# EL_MBRD_T01.net
KiCad netlist of a schematic drawn in Altium Designer
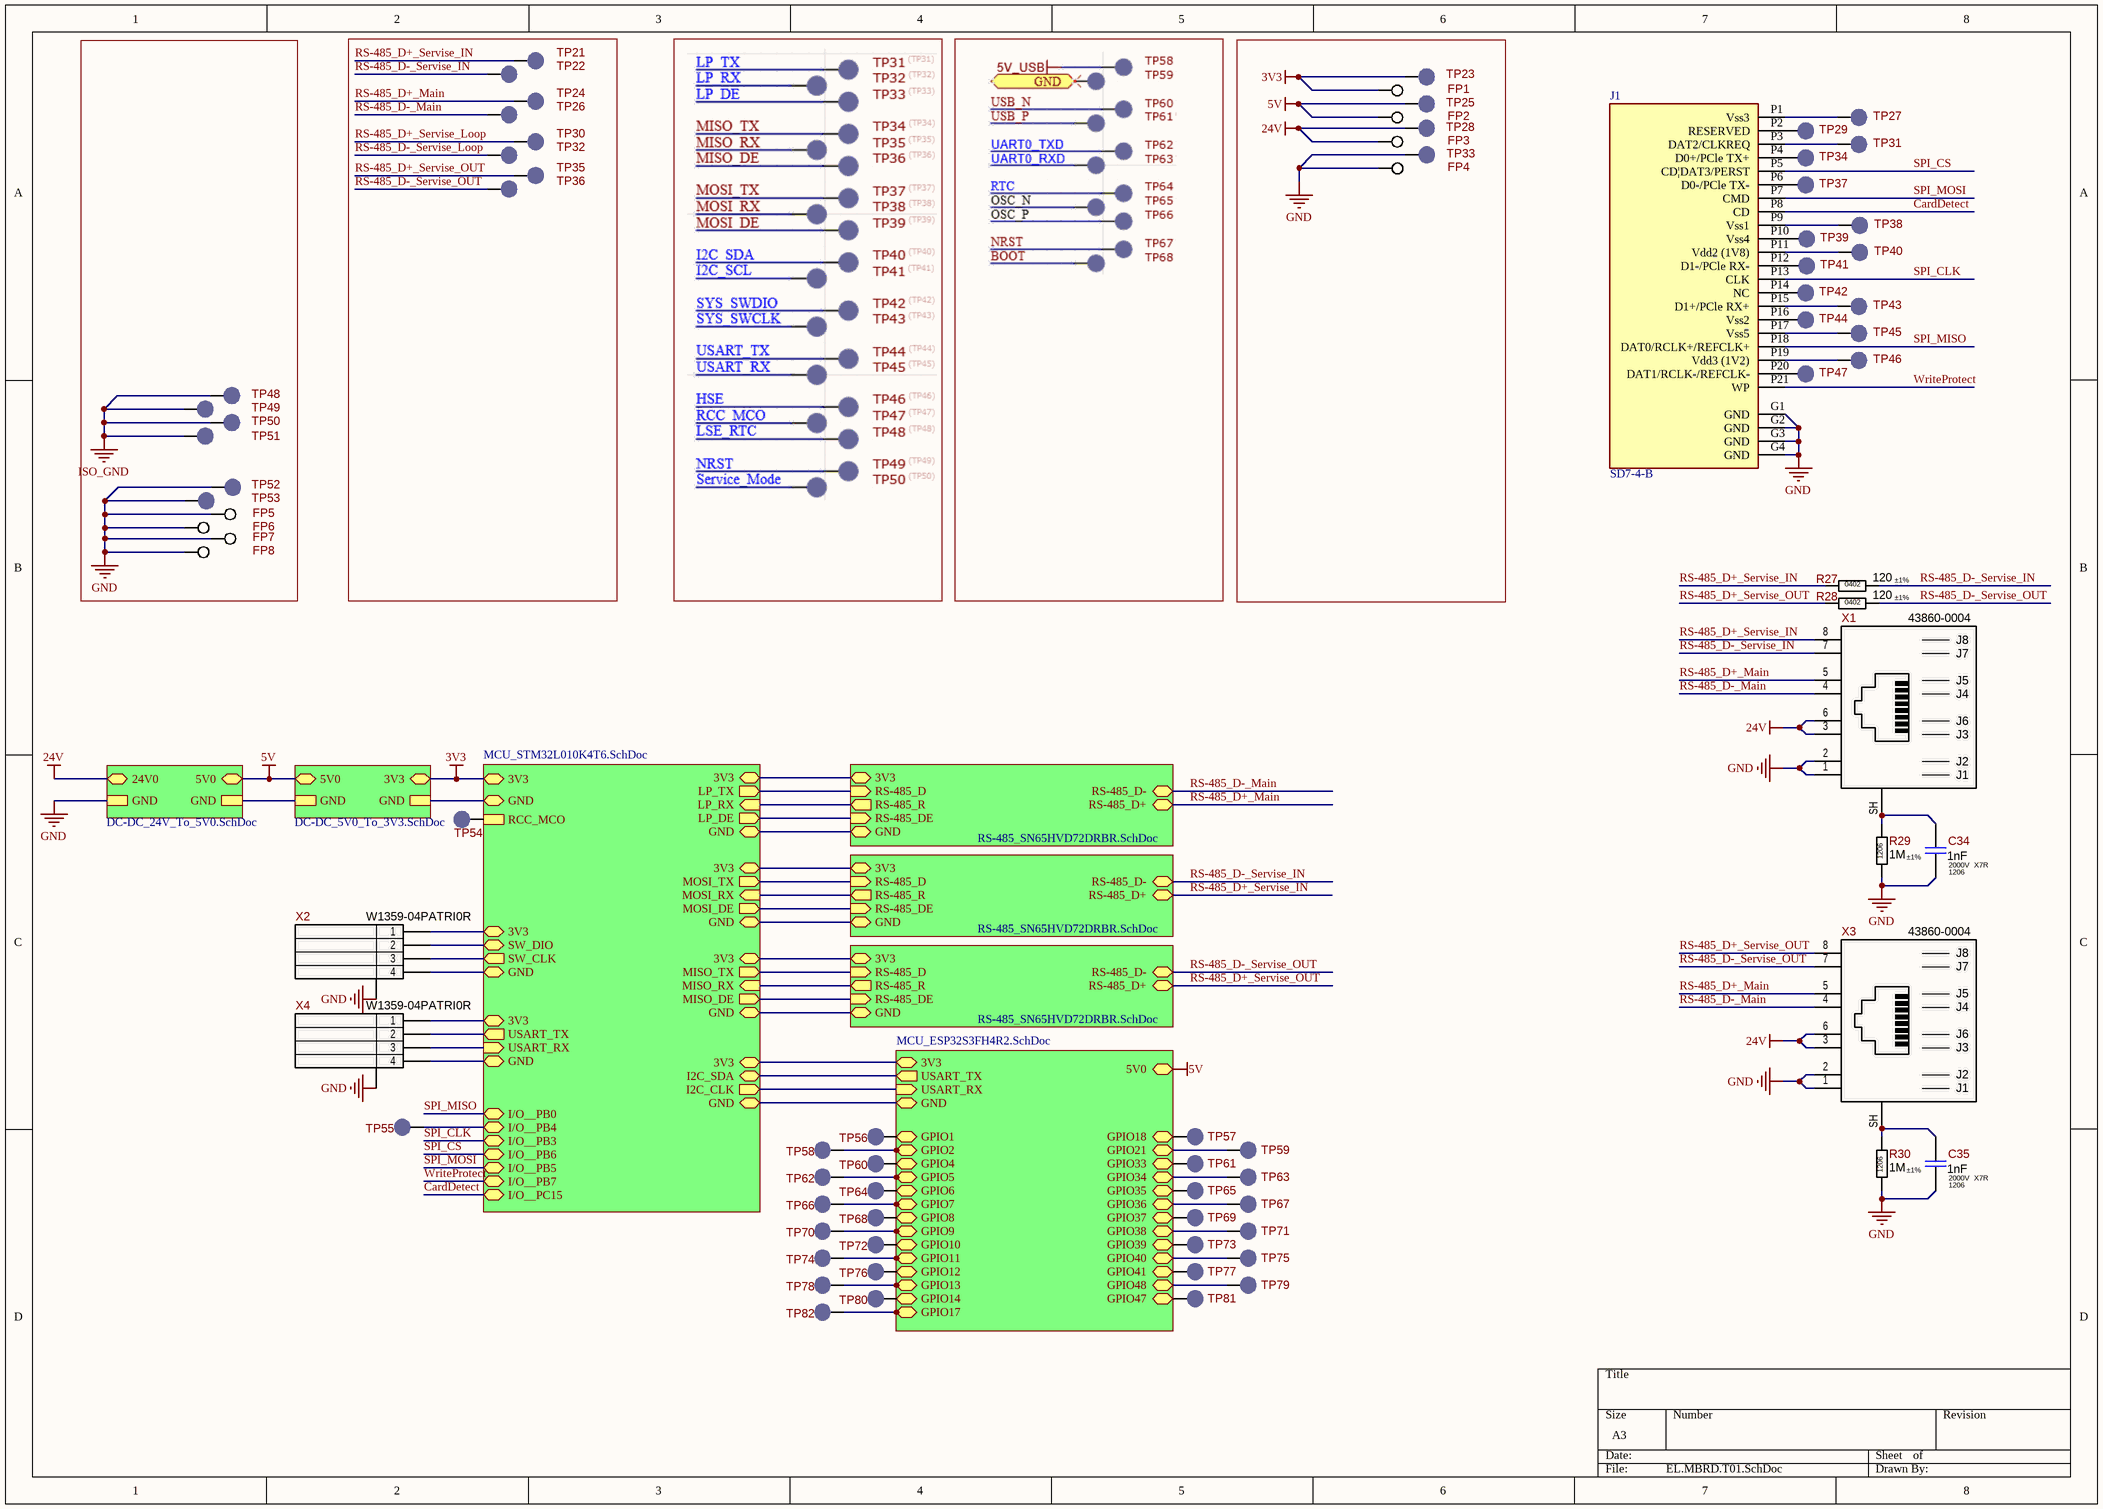
[diagram p0: EL.MBRD.T01.SchDoc]

(export (version "E")
  (design (tool "Eeschema 10.0.6"))
  (components
    (comp (ref "C34")
      (value "1nF")
      (footprint "CAP-1206(3216)X125T20")
      (description "1nF 2000V X7R ±10% 1206 Ceramic Capacitor RoHS")
      (fields
        (field (name "PACKAGE") "1206")
        (field (name "VOLTAGE") "2000V")
        (field (name "DIELECTRIC TYPE") "X7R")
        (field (name "PART NUMBER") "CC1206KKX7RDBB102")
        (field (name "MANUFACTURER") "Yageo")
      )
      (libsource (lib "EL.XXX.T01") (part "Capacitor-NonPolar"))
    )
    (comp (ref "C35")
      (value "1nF")
      (footprint "CAP-1206(3216)X125T20")
      (description "1nF 2000V X7R ±10% 1206 Ceramic Capacitor RoHS")
      (fields
        (field (name "PACKAGE") "1206")
        (field (name "VOLTAGE") "2000V")
        (field (name "DIELECTRIC TYPE") "X7R")
        (field (name "PART NUMBER") "CC1206KKX7RDBB102")
        (field (name "MANUFACTURER") "Yageo")
      )
      (libsource (lib "EL.XXX.T01") (part "Capacitor-NonPolar"))
    )
    (comp (ref "FP1")
      (value "PAD-1.1mm")
      (footprint "PAD-1.1mm")
      (description "1.1mm Pad for Plug-In or Receptacle")
      (fields (field (name "MANUFACTURER") "NONE"))
      (libsource (lib "EL.XXX.T01") (part "Pad"))
    )
    (comp (ref "FP2")
      (value "PAD-1.1mm")
      (footprint "PAD-1.1mm")
      (description "1.1mm Pad for Plug-In or Receptacle")
      (fields (field (name "MANUFACTURER") "NONE"))
      (libsource (lib "EL.XXX.T01") (part "Pad"))
    )
    (comp (ref "FP3")
      (value "PAD-1.1mm")
      (footprint "PAD-1.1mm")
      (description "1.1mm Pad for Plug-In or Receptacle")
      (fields (field (name "MANUFACTURER") "NONE"))
      (libsource (lib "EL.XXX.T01") (part "Pad"))
    )
    (comp (ref "FP4")
      (value "PAD-1.1mm")
      (footprint "PAD-1.1mm")
      (description "1.1mm Pad for Plug-In or Receptacle")
      (fields (field (name "MANUFACTURER") "NONE"))
      (libsource (lib "EL.XXX.T01") (part "Pad"))
    )
    (comp (ref "FP5")
      (value "PAD-1.1mm")
      (footprint "PAD-1.1mm")
      (description "1.1mm Pad for Plug-In or Receptacle")
      (fields (field (name "MANUFACTURER") "NONE"))
      (libsource (lib "EL.XXX.T01") (part "Pad"))
    )
    (comp (ref "FP6")
      (value "PAD-1.1mm")
      (footprint "PAD-1.1mm")
      (description "1.1mm Pad for Plug-In or Receptacle")
      (fields (field (name "MANUFACTURER") "NONE"))
      (libsource (lib "EL.XXX.T01") (part "Pad"))
    )
    (comp (ref "FP7")
      (value "PAD-1.1mm")
      (footprint "PAD-1.1mm")
      (description "1.1mm Pad for Plug-In or Receptacle")
      (fields (field (name "MANUFACTURER") "NONE"))
      (libsource (lib "EL.XXX.T01") (part "Pad"))
    )
    (comp (ref "FP8")
      (value "PAD-1.1mm")
      (footprint "PAD-1.1mm")
      (description "1.1mm Pad for Plug-In or Receptacle")
      (fields (field (name "MANUFACTURER") "NONE"))
      (libsource (lib "EL.XXX.T01") (part "Pad"))
    )
    (comp (ref "J1")
      (value "SD7-4-B")
      (footprint "SAMESKY_SD7-4-B")
      (description "21 (18 + 3) Position Card Connector Secure Digital - SD Surface Mount, Right Angle Gold")
      (fields (field (name "MF") "Same Sky (Formerly CUI Devices)"))
      (libsource (lib "EL.XXX.T01") (part "SD7-4-B"))
    )
    (comp (ref "R27")
      (value "120")
      (footprint "R_ANY_CHIP_0402_HI")
      (description "120 Ohms ±1% 1/16W 0402 Thick Film Resistor")
      (fields
        (field (name "TOLERANCE") "±1%")
        (field (name "PACKAGE") "0402")
        (field (name "PART NUMBER") "RC0402FR-07120RL")
        (field (name "MANUFACTURER") "Yageo")
      )
      (libsource (lib "EL.XXX.T01") (part "Resistor"))
    )
    (comp (ref "R28")
      (value "120")
      (footprint "R_ANY_CHIP_0402_HI")
      (description "120 Ohms ±1% 1/16W 0402 Thick Film Resistor")
      (fields
        (field (name "TOLERANCE") "±1%")
        (field (name "PACKAGE") "0402")
        (field (name "PART NUMBER") "RC0402FR-07120RL")
        (field (name "MANUFACTURER") "Yageo")
      )
      (libsource (lib "EL.XXX.T01") (part "Resistor"))
    )
    (comp (ref "R29")
      (value "1M")
      (footprint "CHV1206-Series")
      (description "1 MOhms ±1%, 1/4W 1206 Thick Film Resistor")
      (fields
        (field (name "TOLERANCE") "±1%")
        (field (name "PACKAGE") "1206")
        (field (name "PART NUMBER") "CHV1206-FX-1004ELF")
        (field (name "MANUFACTURER") "Bourns")
      )
      (libsource (lib "EL.XXX.T01") (part "Resistor"))
    )
    (comp (ref "R30")
      (value "1M")
      (footprint "CHV1206-Series")
      (description "1 MOhms ±1%, 1/4W 1206 Thick Film Resistor")
      (fields
        (field (name "TOLERANCE") "±1%")
        (field (name "PACKAGE") "1206")
        (field (name "PART NUMBER") "CHV1206-FX-1004ELF")
        (field (name "MANUFACTURER") "Bourns")
      )
      (libsource (lib "EL.XXX.T01") (part "Resistor"))
    )
    (comp (ref "TP21")
      (value "LED_LINK")
      (footprint "TP_SMD_2mm")
      (description "Test Point SMD Pad 1.0mm/1.5mm/2mm")
      (fields (field (name "PART NUMBER") "TP-PAD-SMD"))
      (libsource (lib "EL.XXX.T01") (part "Test-Point-SMD-1"))
    )
    (comp (ref "TP22")
      (value "LED_LINK")
      (footprint "TP_SMD_2mm")
      (description "Test Point SMD Pad 1.0mm/1.5mm/2mm")
      (fields (field (name "PART NUMBER") "TP-PAD-SMD"))
      (libsource (lib "EL.XXX.T01") (part "Test-Point-SMD-1"))
    )
    (comp (ref "TP23")
      (value "LED_LINK")
      (footprint "TP_SMD_2mm")
      (description "Test Point SMD Pad 1.0mm/1.5mm/2mm")
      (fields (field (name "PART NUMBER") "TP-PAD-SMD"))
      (libsource (lib "EL.XXX.T01") (part "Test-Point-SMD-1"))
    )
    (comp (ref "TP24")
      (value "LED_LINK")
      (footprint "TP_SMD_2mm")
      (description "Test Point SMD Pad 1.0mm/1.5mm/2mm")
      (fields (field (name "PART NUMBER") "TP-PAD-SMD"))
      (libsource (lib "EL.XXX.T01") (part "Test-Point-SMD-1"))
    )
    (comp (ref "TP25")
      (value "LED_LINK")
      (footprint "TP_SMD_2mm")
      (description "Test Point SMD Pad 1.0mm/1.5mm/2mm")
      (fields (field (name "PART NUMBER") "TP-PAD-SMD"))
      (libsource (lib "EL.XXX.T01") (part "Test-Point-SMD-1"))
    )
    (comp (ref "TP26")
      (value "LED_LINK")
      (footprint "TP_SMD_2mm")
      (description "Test Point SMD Pad 1.0mm/1.5mm/2mm")
      (fields (field (name "PART NUMBER") "TP-PAD-SMD"))
      (libsource (lib "EL.XXX.T01") (part "Test-Point-SMD-1"))
    )
    (comp (ref "TP27")
      (value "LED_LINK")
      (footprint "TP_SMD_2mm")
      (description "Test Point SMD Pad 1.0mm/1.5mm/2mm")
      (fields (field (name "PART NUMBER") "TP-PAD-SMD"))
      (libsource (lib "EL.XXX.T01") (part "Test-Point-SMD-1"))
    )
    (comp (ref "TP28")
      (value "LED_LINK")
      (footprint "TP_SMD_2mm")
      (description "Test Point SMD Pad 1.0mm/1.5mm/2mm")
      (fields (field (name "PART NUMBER") "TP-PAD-SMD"))
      (libsource (lib "EL.XXX.T01") (part "Test-Point-SMD-1"))
    )
    (comp (ref "TP29")
      (value "LED_LINK")
      (footprint "TP_SMD_2mm")
      (description "Test Point SMD Pad 1.0mm/1.5mm/2mm")
      (fields (field (name "PART NUMBER") "TP-PAD-SMD"))
      (libsource (lib "EL.XXX.T01") (part "Test-Point-SMD-1"))
    )
    (comp (ref "TP30")
      (value "LED_LINK")
      (footprint "TP_SMD_2mm")
      (description "Test Point SMD Pad 1.0mm/1.5mm/2mm")
      (fields (field (name "PART NUMBER") "TP-PAD-SMD"))
      (libsource (lib "EL.XXX.T01") (part "Test-Point-SMD-1"))
    )
    (comp (ref "TP31")
      (value "LED_LINK")
      (footprint "TP_SMD_2mm")
      (description "Test Point SMD Pad 1.0mm/1.5mm/2mm")
      (fields (field (name "PART NUMBER") "TP-PAD-SMD"))
      (libsource (lib "EL.XXX.T01") (part "Test-Point-SMD-1"))
    )
    (comp (ref "TP32")
      (value "LED_LINK")
      (footprint "TP_SMD_2mm")
      (description "Test Point SMD Pad 1.0mm/1.5mm/2mm")
      (fields (field (name "PART NUMBER") "TP-PAD-SMD"))
      (libsource (lib "EL.XXX.T01") (part "Test-Point-SMD-1"))
    )
    (comp (ref "TP33")
      (value "LED_LINK")
      (footprint "TP_SMD_2mm")
      (description "Test Point SMD Pad 1.0mm/1.5mm/2mm")
      (fields (field (name "PART NUMBER") "TP-PAD-SMD"))
      (libsource (lib "EL.XXX.T01") (part "Test-Point-SMD-1"))
    )
    (comp (ref "TP34")
      (value "LED_LINK")
      (footprint "TP_SMD_2mm")
      (description "Test Point SMD Pad 1.0mm/1.5mm/2mm")
      (fields (field (name "PART NUMBER") "TP-PAD-SMD"))
      (libsource (lib "EL.XXX.T01") (part "Test-Point-SMD-1"))
    )
    (comp (ref "TP35")
      (value "LED_LINK")
      (footprint "TP_SMD_2mm")
      (description "Test Point SMD Pad 1.0mm/1.5mm/2mm")
      (fields (field (name "PART NUMBER") "TP-PAD-SMD"))
      (libsource (lib "EL.XXX.T01") (part "Test-Point-SMD-1"))
    )
    (comp (ref "TP36")
      (value "LED_LINK")
      (footprint "TP_SMD_2mm")
      (description "Test Point SMD Pad 1.0mm/1.5mm/2mm")
      (fields (field (name "PART NUMBER") "TP-PAD-SMD"))
      (libsource (lib "EL.XXX.T01") (part "Test-Point-SMD-1"))
    )
    (comp (ref "TP37")
      (value "LED_LINK")
      (footprint "TP_SMD_2mm")
      (description "Test Point SMD Pad 1.0mm/1.5mm/2mm")
      (fields (field (name "PART NUMBER") "TP-PAD-SMD"))
      (libsource (lib "EL.XXX.T01") (part "Test-Point-SMD-1"))
    )
    (comp (ref "TP38")
      (value "LED_LINK")
      (footprint "TP_SMD_2mm")
      (description "Test Point SMD Pad 1.0mm/1.5mm/2mm")
      (fields (field (name "PART NUMBER") "TP-PAD-SMD"))
      (libsource (lib "EL.XXX.T01") (part "Test-Point-SMD-1"))
    )
    (comp (ref "TP39")
      (value "LED_LINK")
      (footprint "TP_SMD_2mm")
      (description "Test Point SMD Pad 1.0mm/1.5mm/2mm")
      (fields (field (name "PART NUMBER") "TP-PAD-SMD"))
      (libsource (lib "EL.XXX.T01") (part "Test-Point-SMD-1"))
    )
    (comp (ref "TP40")
      (value "LED_LINK")
      (footprint "TP_SMD_2mm")
      (description "Test Point SMD Pad 1.0mm/1.5mm/2mm")
      (fields (field (name "PART NUMBER") "TP-PAD-SMD"))
      (libsource (lib "EL.XXX.T01") (part "Test-Point-SMD-1"))
    )
    (comp (ref "TP41")
      (value "LED_LINK")
      (footprint "TP_SMD_2mm")
      (description "Test Point SMD Pad 1.0mm/1.5mm/2mm")
      (fields (field (name "PART NUMBER") "TP-PAD-SMD"))
      (libsource (lib "EL.XXX.T01") (part "Test-Point-SMD-1"))
    )
    (comp (ref "TP42")
      (value "LED_LINK")
      (footprint "TP_SMD_2mm")
      (description "Test Point SMD Pad 1.0mm/1.5mm/2mm")
      (fields (field (name "PART NUMBER") "TP-PAD-SMD"))
      (libsource (lib "EL.XXX.T01") (part "Test-Point-SMD-1"))
    )
    (comp (ref "TP43")
      (value "LED_LINK")
      (footprint "TP_SMD_2mm")
      (description "Test Point SMD Pad 1.0mm/1.5mm/2mm")
      (fields (field (name "PART NUMBER") "TP-PAD-SMD"))
      (libsource (lib "EL.XXX.T01") (part "Test-Point-SMD-1"))
    )
    (comp (ref "TP44")
      (value "LED_LINK")
      (footprint "TP_SMD_2mm")
      (description "Test Point SMD Pad 1.0mm/1.5mm/2mm")
      (fields (field (name "PART NUMBER") "TP-PAD-SMD"))
      (libsource (lib "EL.XXX.T01") (part "Test-Point-SMD-1"))
    )
    (comp (ref "TP45")
      (value "LED_LINK")
      (footprint "TP_SMD_2mm")
      (description "Test Point SMD Pad 1.0mm/1.5mm/2mm")
      (fields (field (name "PART NUMBER") "TP-PAD-SMD"))
      (libsource (lib "EL.XXX.T01") (part "Test-Point-SMD-1"))
    )
    (comp (ref "TP46")
      (value "LED_LINK")
      (footprint "TP_SMD_2mm")
      (description "Test Point SMD Pad 1.0mm/1.5mm/2mm")
      (fields (field (name "PART NUMBER") "TP-PAD-SMD"))
      (libsource (lib "EL.XXX.T01") (part "Test-Point-SMD-1"))
    )
    (comp (ref "TP47")
      (value "LED_LINK")
      (footprint "TP_SMD_2mm")
      (description "Test Point SMD Pad 1.0mm/1.5mm/2mm")
      (fields (field (name "PART NUMBER") "TP-PAD-SMD"))
      (libsource (lib "EL.XXX.T01") (part "Test-Point-SMD-1"))
    )
    (comp (ref "TP48")
      (value "LED_LINK")
      (footprint "TP_SMD_2mm")
      (description "Test Point SMD Pad 1.0mm/1.5mm/2mm")
      (fields (field (name "PART NUMBER") "TP-PAD-SMD"))
      (libsource (lib "EL.XXX.T01") (part "Test-Point-SMD-1"))
    )
    (comp (ref "TP49")
      (value "LED_LINK")
      (footprint "TP_SMD_2mm")
      (description "Test Point SMD Pad 1.0mm/1.5mm/2mm")
      (fields (field (name "PART NUMBER") "TP-PAD-SMD"))
      (libsource (lib "EL.XXX.T01") (part "Test-Point-SMD-1"))
    )
    (comp (ref "TP50")
      (value "LED_LINK")
      (footprint "TP_SMD_2mm")
      (description "Test Point SMD Pad 1.0mm/1.5mm/2mm")
      (fields (field (name "PART NUMBER") "TP-PAD-SMD"))
      (libsource (lib "EL.XXX.T01") (part "Test-Point-SMD-1"))
    )
    (comp (ref "TP51")
      (value "LED_LINK")
      (footprint "TP_SMD_2mm")
      (description "Test Point SMD Pad 1.0mm/1.5mm/2mm")
      (fields (field (name "PART NUMBER") "TP-PAD-SMD"))
      (libsource (lib "EL.XXX.T01") (part "Test-Point-SMD-1"))
    )
    (comp (ref "TP52")
      (value "LED_LINK")
      (footprint "TP_SMD_2mm")
      (description "Test Point SMD Pad 1.0mm/1.5mm/2mm")
      (fields (field (name "PART NUMBER") "TP-PAD-SMD"))
      (libsource (lib "EL.XXX.T01") (part "Test-Point-SMD-1"))
    )
    (comp (ref "TP53")
      (value "LED_LINK")
      (footprint "TP_SMD_2mm")
      (description "Test Point SMD Pad 1.0mm/1.5mm/2mm")
      (fields (field (name "PART NUMBER") "TP-PAD-SMD"))
      (libsource (lib "EL.XXX.T01") (part "Test-Point-SMD-1"))
    )
    (comp (ref "TP54")
      (value "LED_LINK")
      (footprint "TP_SMD_2mm")
      (description "Test Point SMD Pad 1.0mm/1.5mm/2mm")
      (fields (field (name "PART NUMBER") "TP-PAD-SMD"))
      (libsource (lib "EL.XXX.T01") (part "Test-Point-SMD-1"))
    )
    (comp (ref "TP55")
      (value "LED_LINK")
      (footprint "TP_SMD_2mm")
      (description "Test Point SMD Pad 1.0mm/1.5mm/2mm")
      (fields (field (name "PART NUMBER") "TP-PAD-SMD"))
      (libsource (lib "EL.XXX.T01") (part "Test-Point-SMD-1"))
    )
    (comp (ref "TP56")
      (value "LED_LINK")
      (footprint "TP_SMD_2mm")
      (description "Test Point SMD Pad 1.0mm/1.5mm/2mm")
      (fields (field (name "PART NUMBER") "TP-PAD-SMD"))
      (libsource (lib "EL.XXX.T01") (part "Test-Point-SMD-1"))
    )
    (comp (ref "TP57")
      (value "LED_LINK")
      (footprint "TP_SMD_2mm")
      (description "Test Point SMD Pad 1.0mm/1.5mm/2mm")
      (fields (field (name "PART NUMBER") "TP-PAD-SMD"))
      (libsource (lib "EL.XXX.T01") (part "Test-Point-SMD-1"))
    )
    (comp (ref "TP58")
      (value "LED_LINK")
      (footprint "TP_SMD_2mm")
      (description "Test Point SMD Pad 1.0mm/1.5mm/2mm")
      (fields (field (name "PART NUMBER") "TP-PAD-SMD"))
      (libsource (lib "EL.XXX.T01") (part "Test-Point-SMD-1"))
    )
    (comp (ref "TP59")
      (value "LED_LINK")
      (footprint "TP_SMD_2mm")
      (description "Test Point SMD Pad 1.0mm/1.5mm/2mm")
      (fields (field (name "PART NUMBER") "TP-PAD-SMD"))
      (libsource (lib "EL.XXX.T01") (part "Test-Point-SMD-1"))
    )
    (comp (ref "TP60")
      (value "LED_LINK")
      (footprint "TP_SMD_2mm")
      (description "Test Point SMD Pad 1.0mm/1.5mm/2mm")
      (fields (field (name "PART NUMBER") "TP-PAD-SMD"))
      (libsource (lib "EL.XXX.T01") (part "Test-Point-SMD-1"))
    )
    (comp (ref "TP61")
      (value "LED_LINK")
      (footprint "TP_SMD_2mm")
      (description "Test Point SMD Pad 1.0mm/1.5mm/2mm")
      (fields (field (name "PART NUMBER") "TP-PAD-SMD"))
      (libsource (lib "EL.XXX.T01") (part "Test-Point-SMD-1"))
    )
    (comp (ref "TP62")
      (value "LED_LINK")
      (footprint "TP_SMD_2mm")
      (description "Test Point SMD Pad 1.0mm/1.5mm/2mm")
      (fields (field (name "PART NUMBER") "TP-PAD-SMD"))
      (libsource (lib "EL.XXX.T01") (part "Test-Point-SMD-1"))
    )
    (comp (ref "TP63")
      (value "LED_LINK")
      (footprint "TP_SMD_2mm")
      (description "Test Point SMD Pad 1.0mm/1.5mm/2mm")
      (fields (field (name "PART NUMBER") "TP-PAD-SMD"))
      (libsource (lib "EL.XXX.T01") (part "Test-Point-SMD-1"))
    )
    (comp (ref "TP64")
      (value "LED_LINK")
      (footprint "TP_SMD_2mm")
      (description "Test Point SMD Pad 1.0mm/1.5mm/2mm")
      (fields (field (name "PART NUMBER") "TP-PAD-SMD"))
      (libsource (lib "EL.XXX.T01") (part "Test-Point-SMD-1"))
    )
    (comp (ref "TP65")
      (value "LED_LINK")
      (footprint "TP_SMD_2mm")
      (description "Test Point SMD Pad 1.0mm/1.5mm/2mm")
      (fields (field (name "PART NUMBER") "TP-PAD-SMD"))
      (libsource (lib "EL.XXX.T01") (part "Test-Point-SMD-1"))
    )
    (comp (ref "TP66")
      (value "LED_LINK")
      (footprint "TP_SMD_2mm")
      (description "Test Point SMD Pad 1.0mm/1.5mm/2mm")
      (fields (field (name "PART NUMBER") "TP-PAD-SMD"))
      (libsource (lib "EL.XXX.T01") (part "Test-Point-SMD-1"))
    )
    (comp (ref "TP67")
      (value "LED_LINK")
      (footprint "TP_SMD_2mm")
      (description "Test Point SMD Pad 1.0mm/1.5mm/2mm")
      (fields (field (name "PART NUMBER") "TP-PAD-SMD"))
      (libsource (lib "EL.XXX.T01") (part "Test-Point-SMD-1"))
    )
    (comp (ref "TP68")
      (value "LED_LINK")
      (footprint "TP_SMD_2mm")
      (description "Test Point SMD Pad 1.0mm/1.5mm/2mm")
      (fields (field (name "PART NUMBER") "TP-PAD-SMD"))
      (libsource (lib "EL.XXX.T01") (part "Test-Point-SMD-1"))
    )
    (comp (ref "TP69")
      (value "LED_LINK")
      (footprint "TP_SMD_2mm")
      (description "Test Point SMD Pad 1.0mm/1.5mm/2mm")
      (fields (field (name "PART NUMBER") "TP-PAD-SMD"))
      (libsource (lib "EL.XXX.T01") (part "Test-Point-SMD-1"))
    )
    (comp (ref "TP70")
      (value "LED_LINK")
      (footprint "TP_SMD_2mm")
      (description "Test Point SMD Pad 1.0mm/1.5mm/2mm")
      (fields (field (name "PART NUMBER") "TP-PAD-SMD"))
      (libsource (lib "EL.XXX.T01") (part "Test-Point-SMD-1"))
    )
    (comp (ref "TP71")
      (value "LED_LINK")
      (footprint "TP_SMD_2mm")
      (description "Test Point SMD Pad 1.0mm/1.5mm/2mm")
      (fields (field (name "PART NUMBER") "TP-PAD-SMD"))
      (libsource (lib "EL.XXX.T01") (part "Test-Point-SMD-1"))
    )
    (comp (ref "TP72")
      (value "LED_LINK")
      (footprint "TP_SMD_2mm")
      (description "Test Point SMD Pad 1.0mm/1.5mm/2mm")
      (fields (field (name "PART NUMBER") "TP-PAD-SMD"))
      (libsource (lib "EL.XXX.T01") (part "Test-Point-SMD-1"))
    )
    (comp (ref "TP73")
      (value "LED_LINK")
      (footprint "TP_SMD_2mm")
      (description "Test Point SMD Pad 1.0mm/1.5mm/2mm")
      (fields (field (name "PART NUMBER") "TP-PAD-SMD"))
      (libsource (lib "EL.XXX.T01") (part "Test-Point-SMD-1"))
    )
    (comp (ref "TP74")
      (value "LED_LINK")
      (footprint "TP_SMD_2mm")
      (description "Test Point SMD Pad 1.0mm/1.5mm/2mm")
      (fields (field (name "PART NUMBER") "TP-PAD-SMD"))
      (libsource (lib "EL.XXX.T01") (part "Test-Point-SMD-1"))
    )
    (comp (ref "TP75")
      (value "LED_LINK")
      (footprint "TP_SMD_2mm")
      (description "Test Point SMD Pad 1.0mm/1.5mm/2mm")
      (fields (field (name "PART NUMBER") "TP-PAD-SMD"))
      (libsource (lib "EL.XXX.T01") (part "Test-Point-SMD-1"))
    )
    (comp (ref "TP76")
      (value "LED_LINK")
      (footprint "TP_SMD_2mm")
      (description "Test Point SMD Pad 1.0mm/1.5mm/2mm")
      (fields (field (name "PART NUMBER") "TP-PAD-SMD"))
      (libsource (lib "EL.XXX.T01") (part "Test-Point-SMD-1"))
    )
    (comp (ref "TP77")
      (value "LED_LINK")
      (footprint "TP_SMD_2mm")
      (description "Test Point SMD Pad 1.0mm/1.5mm/2mm")
      (fields (field (name "PART NUMBER") "TP-PAD-SMD"))
      (libsource (lib "EL.XXX.T01") (part "Test-Point-SMD-1"))
    )
    (comp (ref "TP78")
      (value "LED_LINK")
      (footprint "TP_SMD_2mm")
      (description "Test Point SMD Pad 1.0mm/1.5mm/2mm")
      (fields (field (name "PART NUMBER") "TP-PAD-SMD"))
      (libsource (lib "EL.XXX.T01") (part "Test-Point-SMD-1"))
    )
    (comp (ref "TP79")
      (value "LED_LINK")
      (footprint "TP_SMD_2mm")
      (description "Test Point SMD Pad 1.0mm/1.5mm/2mm")
      (fields (field (name "PART NUMBER") "TP-PAD-SMD"))
      (libsource (lib "EL.XXX.T01") (part "Test-Point-SMD-1"))
    )
    (comp (ref "TP80")
      (value "LED_LINK")
      (footprint "TP_SMD_2mm")
      (description "Test Point SMD Pad 1.0mm/1.5mm/2mm")
      (fields (field (name "PART NUMBER") "TP-PAD-SMD"))
      (libsource (lib "EL.XXX.T01") (part "Test-Point-SMD-1"))
    )
    (comp (ref "TP81")
      (value "LED_LINK")
      (footprint "TP_SMD_2mm")
      (description "Test Point SMD Pad 1.0mm/1.5mm/2mm")
      (fields (field (name "PART NUMBER") "TP-PAD-SMD"))
      (libsource (lib "EL.XXX.T01") (part "Test-Point-SMD-1"))
    )
    (comp (ref "TP82")
      (value "LED_LINK")
      (footprint "TP_SMD_2mm")
      (description "Test Point SMD Pad 1.0mm/1.5mm/2mm")
      (fields (field (name "PART NUMBER") "TP-PAD-SMD"))
      (libsource (lib "EL.XXX.T01") (part "Test-Point-SMD-1"))
    )
    (comp (ref "X1")
      (value "43860-0004")
      (footprint "43860-0004")
      (description "RJ45 8P8C Shielded Cat 3 10 Base-T Connector")
      (fields (field (name "PART NUMBER") "43860-0004") (field (name "MANUFACTURER") "Molex"))
      (libsource (lib "EL.XXX.T01") (part "43860-0004"))
    )
    (comp (ref "X2")
      (value "W1359-04PATRI0R")
      (footprint "W1359-04PATXI0R_DBG")
      (description "1.25mm Wire-to-Board Header, Vertical, SMT, 4 pin")
      (fields
        (field (name "PART NUMBER") "W1359-04PATRI0R")
        (field (name "MANUFACTURER") "Hsuan Mao Technology")
      )
      (libsource (lib "EL.XXX.T01") (part "General-4-Pin-MP"))
    )
    (comp (ref "X3")
      (value "43860-0004")
      (footprint "43860-0004")
      (description "RJ45 8P8C Shielded Cat 3 10 Base-T Connector")
      (fields (field (name "PART NUMBER") "43860-0004") (field (name "MANUFACTURER") "Molex"))
      (libsource (lib "EL.XXX.T01") (part "43860-0004"))
    )
    (comp (ref "X4")
      (value "W1359-04PATRI0R")
      (footprint "W1359-04PATXI0R_DBG")
      (description "1.25mm Wire-to-Board Header, Vertical, SMT, 4 pin")
      (fields
        (field (name "PART NUMBER") "W1359-04PATRI0R")
        (field (name "MANUFACTURER") "Hsuan Mao Technology")
      )
      (libsource (lib "EL.XXX.T01") (part "General-4-Pin-MP"))
    )
  )
  (nets
    (net (code "4") (name "/3V3_3") (class "Default")
      (node (ref "X2") (pin "1") (pinfunction "1_1") (pintype "passive"))
    )
    (net (code "6") (name "/3V3_5") (class "Default")
      (node (ref "X4") (pin "1") (pinfunction "1_1") (pintype "passive"))
    )
    (net (code "8") (name "/CardDetect") (class "Default")
      (node (ref "J1") (pin "P8") (pinfunction "CD_P8") (pintype "passive"))
    )
    (net (code "9") (name "/GND") (class "Default")
      (node (ref "X2") (pin "4") (pinfunction "4_4") (pintype "passive"))
    )
    (net (code "14") (name "/GND_5") (class "Default")
      (node (ref "X4") (pin "4") (pinfunction "4_4") (pintype "passive"))
    )
    (net (code "19") (name "/GPIO2") (class "Default") (node (ref "TP58") (pin "1") (pintype "passive")))
    (net (code "21") (name "/GPIO5") (class "Default") (node (ref "TP62") (pin "1") (pintype "passive")))
    (net (code "23") (name "/GPIO7") (class "Default") (node (ref "TP66") (pin "1") (pintype "passive")))
    (net (code "25") (name "/GPIO9") (class "Default") (node (ref "TP70") (pin "1") (pintype "passive")))
    (net (code "27") (name "/GPIO11") (class "Default") (node (ref "TP74") (pin "1") (pintype "passive")))
    (net (code "29") (name "/GPIO13") (class "Default") (node (ref "TP78") (pin "1") (pintype "passive")))
    (net (code "31") (name "/GPIO17") (class "Default") (node (ref "TP82") (pin "1") (pintype "passive")))
    (net (code "46") (name "/I{slash}O__PB4") (class "Default")
      (node (ref "TP55") (pin "1") (pintype "passive"))
    )
    (net (code "53") (name "/RCC_MCO") (class "Default") (node (ref "TP54") (pin "1") (pintype "passive")))
    (net (code "54") (name "/RS-485_D+_Main") (class "Default")
      (node (ref "TP24") (pin "1") (pintype "passive"))
      (node (ref "X1") (pin "5") (pinfunction "CT_5") (pintype "passive"))
      (node (ref "X3") (pin "5") (pinfunction "CT_5") (pintype "passive"))
    )
    (net (code "55") (name "/RS-485_D+_Servise_IN") (class "Default")
      (node (ref "R27") (pin "1") (pintype "passive"))
      (node (ref "TP21") (pin "1") (pintype "passive"))
      (node (ref "X1") (pin "8") (pinfunction "TD2+_8") (pintype "passive"))
    )
    (net (code "56") (name "/RS-485_D+_Servise_Loop") (class "Default")
      (node (ref "TP30") (pin "1") (pintype "passive"))
    )
    (net (code "57") (name "/RS-485_D+_Servise_OUT") (class "Default")
      (node (ref "R28") (pin "1") (pintype "passive"))
      (node (ref "TP35") (pin "1") (pintype "passive"))
      (node (ref "X3") (pin "8") (pinfunction "TD2+_8") (pintype "passive"))
    )
    (net (code "58") (name "/RS-485_D-_Main") (class "Default")
      (node (ref "TP26") (pin "1") (pintype "passive"))
      (node (ref "X1") (pin "4") (pinfunction "TD3+_4") (pintype "passive"))
      (node (ref "X3") (pin "4") (pinfunction "TD3+_4") (pintype "passive"))
    )
    (net (code "59") (name "/RS-485_D-_Servise_IN") (class "Default")
      (node (ref "R27") (pin "2") (pintype "passive"))
      (node (ref "TP22") (pin "1") (pintype "passive"))
      (node (ref "X1") (pin "7") (pinfunction "TD2-_7") (pintype "passive"))
    )
    (net (code "60") (name "/RS-485_D-_Servise_Loop") (class "Default")
      (node (ref "TP32") (pin "1") (pintype "passive"))
    )
    (net (code "61") (name "/RS-485_D-_Servise_OUT") (class "Default")
      (node (ref "R28") (pin "2") (pintype "passive"))
      (node (ref "TP36") (pin "1") (pintype "passive"))
      (node (ref "X3") (pin "7") (pinfunction "TD2-_7") (pintype "passive"))
    )
    (net (code "65") (name "/SPI_CLK") (class "Default")
      (node (ref "J1") (pin "P13") (pinfunction "CLK_P13") (pintype "passive"))
    )
    (net (code "66") (name "/SPI_CS") (class "Default")
      (node (ref "J1") (pin "P5") (pinfunction "CD¦DAT3/PERST_P5") (pintype "passive"))
    )
    (net (code "67") (name "/SPI_MISO") (class "Default")
      (node (ref "J1") (pin "P18") (pinfunction "DAT0/RCLK+/REFCLK+_P18") (pintype "passive"))
    )
    (net (code "69") (name "/SW_CLK") (class "Default")
      (node (ref "X2") (pin "3") (pinfunction "3_3") (pintype "passive"))
    )
    (net (code "70") (name "/SW_DIO") (class "Default")
      (node (ref "X2") (pin "2") (pinfunction "2_2") (pintype "passive"))
    )
    (net (code "71") (name "/USART_RX") (class "Default")
      (node (ref "X4") (pin "3") (pinfunction "3_3") (pintype "passive"))
    )
    (net (code "72") (name "/USART_TX") (class "Default")
      (node (ref "X4") (pin "2") (pinfunction "2_2") (pintype "passive"))
    )
    (net (code "74") (name "/WriteProtect") (class "Default")
      (node (ref "J1") (pin "P21") (pinfunction "WP_P21") (pintype "passive"))
    )
    (net (code "75") (name "3V3") (class "Default")
      (node (ref "FP1") (pin "1") (pintype "passive"))
      (node (ref "TP23") (pin "1") (pintype "passive"))
    )
    (net (code "76") (name "5V") (class "Default")
      (node (ref "FP2") (pin "1") (pintype "passive"))
      (node (ref "TP25") (pin "1") (pintype "passive"))
    )
    (net (code "77") (name "24V") (class "Default")
      (node (ref "FP3") (pin "1") (pintype "passive"))
      (node (ref "TP28") (pin "1") (pintype "passive"))
      (node (ref "X1") (pin "3") (pinfunction "TD3-_3") (pintype "passive"))
      (node (ref "X1") (pin "6") (pinfunction "CT_6") (pintype "passive"))
      (node (ref "X3") (pin "3") (pinfunction "TD3-_3") (pintype "passive"))
      (node (ref "X3") (pin "6") (pinfunction "CT_6") (pintype "passive"))
    )
    (net (code "78") (name "GND") (class "Default")
      (node (ref "C34") (pin "2") (pinfunction "2_2") (pintype "passive"))
      (node (ref "C35") (pin "2") (pinfunction "2_2") (pintype "passive"))
      (node (ref "FP4") (pin "1") (pintype "passive"))
      (node (ref "FP5") (pin "1") (pintype "passive"))
      (node (ref "FP6") (pin "1") (pintype "passive"))
      (node (ref "FP7") (pin "1") (pintype "passive"))
      (node (ref "FP8") (pin "1") (pintype "passive"))
      (node (ref "J1") (pin "G1") (pinfunction "GND_G1") (pintype "power_in"))
      (node (ref "J1") (pin "G2") (pinfunction "GND_G2") (pintype "power_in"))
      (node (ref "J1") (pin "G3") (pinfunction "GND_G3") (pintype "power_in"))
      (node (ref "J1") (pin "G4") (pinfunction "GND_G4") (pintype "power_in"))
      (node (ref "R29") (pin "2") (pintype "passive"))
      (node (ref "R30") (pin "2") (pintype "passive"))
      (node (ref "TP33") (pin "1") (pintype "passive"))
      (node (ref "TP52") (pin "1") (pintype "passive"))
      (node (ref "TP53") (pin "1") (pintype "passive"))
      (node (ref "X1") (pin "1") (pinfunction "TD4-_1") (pintype "passive"))
      (node (ref "X1") (pin "2") (pinfunction "TD4+_2") (pintype "passive"))
      (node (ref "X2") (pin "MP") (pinfunction "MountPad_MP") (pintype "passive"))
      (node (ref "X3") (pin "1") (pinfunction "TD4-_1") (pintype "passive"))
      (node (ref "X3") (pin "2") (pinfunction "TD4+_2") (pintype "passive"))
      (node (ref "X4") (pin "MP") (pinfunction "MountPad_MP") (pintype "passive"))
    )
    (net (code "79") (name "ISO_GND") (class "Default")
      (node (ref "TP48") (pin "1") (pintype "passive"))
      (node (ref "TP49") (pin "1") (pintype "passive"))
      (node (ref "TP50") (pin "1") (pintype "passive"))
      (node (ref "TP51") (pin "1") (pintype "passive"))
    )
    (net (code "80") (name "Net-(J1-D1+{slash}PCle_RX+)") (class "Default")
      (node (ref "J1") (pin "P15") (pinfunction "D1+/PCle_RX+_P15") (pintype "passive"))
      (node (ref "TP43") (pin "1") (pintype "passive"))
    )
    (net (code "81") (name "Net-(J1-D1-{slash}PCle_RX-)") (class "Default")
      (node (ref "J1") (pin "P12") (pinfunction "D1-/PCle_RX-_P12") (pintype "passive"))
      (node (ref "TP41") (pin "1") (pintype "passive"))
    )
    (net (code "82") (name "Net-(J1-DAT2{slash}CLKREQ)") (class "Default")
      (node (ref "J1") (pin "P3") (pinfunction "DAT2/CLKREQ_P3") (pintype "passive"))
      (node (ref "TP31") (pin "1") (pintype "passive"))
    )
    (net (code "83") (name "Net-(J1-Vdd3_(1V2))") (class "Default")
      (node (ref "J1") (pin "P19") (pinfunction "Vdd3_(1V2)_P19") (pintype "passive"))
      (node (ref "TP46") (pin "1") (pintype "passive"))
    )
    (net (code "84") (name "Net-(J1-Vss3)") (class "Default")
      (node (ref "J1") (pin "P1") (pinfunction "Vss3_P1") (pintype "passive"))
      (node (ref "TP27") (pin "1") (pintype "passive"))
    )
    (net (code "85") (name "Net-(J1-Vss4)") (class "Default")
      (node (ref "J1") (pin "P10") (pinfunction "Vss4_P10") (pintype "passive"))
      (node (ref "TP39") (pin "1") (pintype "passive"))
    )
    (net (code "86") (name "Net-(J1-Vss5)") (class "Default")
      (node (ref "J1") (pin "P17") (pinfunction "Vss5_P17") (pintype "passive"))
      (node (ref "TP45") (pin "1") (pintype "passive"))
    )
    (net (code "87") (name "Net-(X1-Shield)") (class "Default")
      (node (ref "C34") (pin "1") (pinfunction "1_1") (pintype "passive"))
      (node (ref "R29") (pin "1") (pintype "passive"))
      (node (ref "X1") (pin "SH") (pinfunction "Shield_SH") (pintype "passive"))
    )
    (net (code "88") (name "Net-(X3-Shield)") (class "Default")
      (node (ref "C35") (pin "1") (pinfunction "1_1") (pintype "passive"))
      (node (ref "R30") (pin "1") (pintype "passive"))
      (node (ref "X3") (pin "SH") (pinfunction "Shield_SH") (pintype "passive"))
    )
    (net (code "89") (name "unconnected-(J1-CMD-PadP7)") (class "Default")
      (node (ref "J1") (pin "P7") (pinfunction "CMD_P7") (pintype "passive"))
    )
    (net (code "90") (name "unconnected-(J1-D0+{slash}PCle_TX+-PadP4)") (class "Default")
      (node (ref "J1") (pin "P4") (pinfunction "D0+/PCle_TX+_P4") (pintype "passive"))
    )
    (net (code "91") (name "unconnected-(J1-D0-{slash}PCle_TX--PadP6)") (class "Default")
      (node (ref "J1") (pin "P6") (pinfunction "D0-/PCle_TX-_P6") (pintype "passive"))
    )
    (net (code "92") (name "unconnected-(J1-DAT1{slash}RCLK-{slash}REFCLK--PadP20)") (class "Default")
      (node (ref "J1") (pin "P20") (pinfunction "DAT1/RCLK-/REFCLK-_P20") (pintype "passive"))
    )
    (net (code "93") (name "unconnected-(J1-NC-PadP14)") (class "Default")
      (node (ref "J1") (pin "P14") (pinfunction "NC_P14") (pintype "passive"))
    )
    (net (code "94") (name "unconnected-(J1-RESERVED-PadP2)") (class "Default")
      (node (ref "J1") (pin "P2") (pinfunction "RESERVED_P2") (pintype "passive"))
    )
    (net (code "95") (name "unconnected-(J1-Vdd2_(1V8)-PadP11)") (class "Default")
      (node (ref "J1") (pin "P11") (pinfunction "Vdd2_(1V8)_P11") (pintype "passive"))
    )
    (net (code "96") (name "unconnected-(J1-Vss1-PadP9)") (class "Default")
      (node (ref "J1") (pin "P9") (pinfunction "Vss1_P9") (pintype "passive"))
    )
    (net (code "97") (name "unconnected-(J1-Vss2-PadP16)") (class "Default")
      (node (ref "J1") (pin "P16") (pinfunction "Vss2_P16") (pintype "passive"))
    )
    (net (code "98") (name "unconnected-(TP29-Pad1)") (class "Default")
      (node (ref "TP29") (pin "1") (pintype "passive"))
    )
    (net (code "99") (name "unconnected-(TP34-Pad1)") (class "Default")
      (node (ref "TP34") (pin "1") (pintype "passive"))
    )
    (net (code "100") (name "unconnected-(TP37-Pad1)") (class "Default")
      (node (ref "TP37") (pin "1") (pintype "passive"))
    )
    (net (code "101") (name "unconnected-(TP38-Pad1)") (class "Default")
      (node (ref "TP38") (pin "1") (pintype "passive"))
    )
    (net (code "102") (name "unconnected-(TP40-Pad1)") (class "Default")
      (node (ref "TP40") (pin "1") (pintype "passive"))
    )
    (net (code "103") (name "unconnected-(TP42-Pad1)") (class "Default")
      (node (ref "TP42") (pin "1") (pintype "passive"))
    )
    (net (code "104") (name "unconnected-(TP44-Pad1)") (class "Default")
      (node (ref "TP44") (pin "1") (pintype "passive"))
    )
    (net (code "105") (name "unconnected-(TP47-Pad1)") (class "Default")
      (node (ref "TP47") (pin "1") (pintype "passive"))
    )
    (net (code "106") (name "unconnected-(TP56-Pad1)") (class "Default")
      (node (ref "TP56") (pin "1") (pintype "passive"))
    )
    (net (code "107") (name "unconnected-(TP57-Pad1)") (class "Default")
      (node (ref "TP57") (pin "1") (pintype "passive"))
    )
    (net (code "108") (name "unconnected-(TP59-Pad1)") (class "Default")
      (node (ref "TP59") (pin "1") (pintype "passive"))
    )
    (net (code "109") (name "unconnected-(TP60-Pad1)") (class "Default")
      (node (ref "TP60") (pin "1") (pintype "passive"))
    )
    (net (code "110") (name "unconnected-(TP61-Pad1)") (class "Default")
      (node (ref "TP61") (pin "1") (pintype "passive"))
    )
    (net (code "111") (name "unconnected-(TP63-Pad1)") (class "Default")
      (node (ref "TP63") (pin "1") (pintype "passive"))
    )
    (net (code "112") (name "unconnected-(TP64-Pad1)") (class "Default")
      (node (ref "TP64") (pin "1") (pintype "passive"))
    )
    (net (code "113") (name "unconnected-(TP65-Pad1)") (class "Default")
      (node (ref "TP65") (pin "1") (pintype "passive"))
    )
    (net (code "114") (name "unconnected-(TP67-Pad1)") (class "Default")
      (node (ref "TP67") (pin "1") (pintype "passive"))
    )
    (net (code "115") (name "unconnected-(TP68-Pad1)") (class "Default")
      (node (ref "TP68") (pin "1") (pintype "passive"))
    )
    (net (code "116") (name "unconnected-(TP69-Pad1)") (class "Default")
      (node (ref "TP69") (pin "1") (pintype "passive"))
    )
    (net (code "117") (name "unconnected-(TP71-Pad1)") (class "Default")
      (node (ref "TP71") (pin "1") (pintype "passive"))
    )
    (net (code "118") (name "unconnected-(TP72-Pad1)") (class "Default")
      (node (ref "TP72") (pin "1") (pintype "passive"))
    )
    (net (code "119") (name "unconnected-(TP73-Pad1)") (class "Default")
      (node (ref "TP73") (pin "1") (pintype "passive"))
    )
    (net (code "120") (name "unconnected-(TP75-Pad1)") (class "Default")
      (node (ref "TP75") (pin "1") (pintype "passive"))
    )
    (net (code "121") (name "unconnected-(TP76-Pad1)") (class "Default")
      (node (ref "TP76") (pin "1") (pintype "passive"))
    )
    (net (code "122") (name "unconnected-(TP77-Pad1)") (class "Default")
      (node (ref "TP77") (pin "1") (pintype "passive"))
    )
    (net (code "123") (name "unconnected-(TP79-Pad1)") (class "Default")
      (node (ref "TP79") (pin "1") (pintype "passive"))
    )
    (net (code "124") (name "unconnected-(TP80-Pad1)") (class "Default")
      (node (ref "TP80") (pin "1") (pintype "passive"))
    )
    (net (code "125") (name "unconnected-(TP81-Pad1)") (class "Default")
      (node (ref "TP81") (pin "1") (pintype "passive"))
    )
  )
)
